# Connectors.net
KiCad netlist of a schematic drawn in Altium Designer
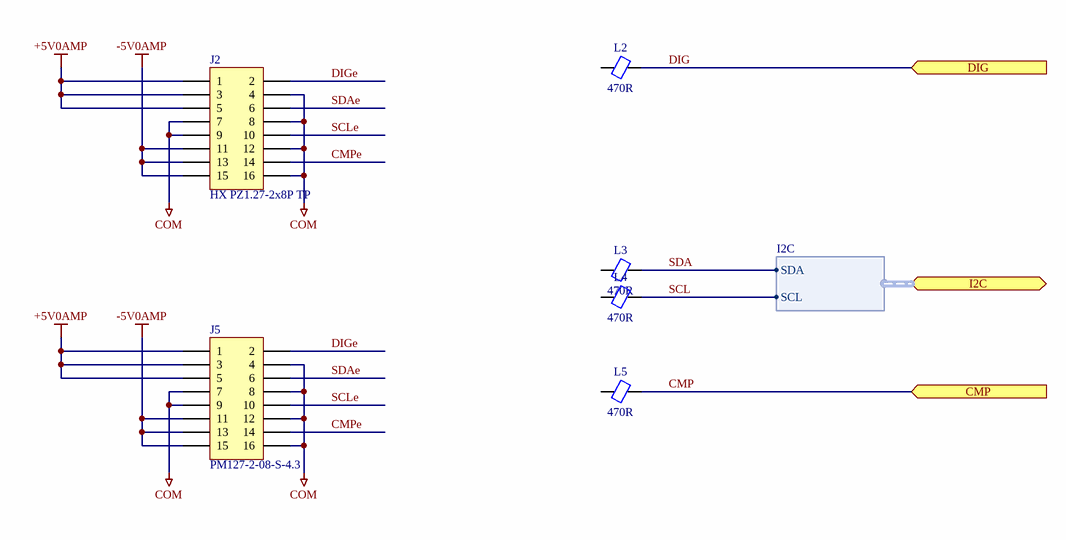
[diagram p0: Connectors.SchDoc]

(export (version "E")
  (design (tool "Eeschema 10.0.6"))
  (components
    (comp (ref "J2")
      (value "HX PZ1.27-2x8P TP")
      (footprint "HANXIA_HX PZ1.27-2x8P TP")
      (description "CONN HEADER 16POS 1.27mm DUAL ROW SMD")
      (fields (field (name "VENDOR 1 PART NUMBER") "C41376040") (field (name "CREATEDBY") "Judd Foster"))
      (libsource (lib "Component Library") (part "CONN,Hdr,2x8 Pin,1.27mm,SMD"))
    )
    (comp (ref "J5")
      (value "PM127-2-08-S-4.3")
      (footprint "HCTL_PM127-2-08-S-4.3")
      (description "CONN SOCKET 16POS 1.27mm DUAL ROW SMD")
      (fields (field (name "VENDOR 1 PART NUMBER") "C3975134") (field (name "CREATEDBY") "Judd Foster"))
      (libsource (lib "Component Library") (part "CONN,Rcpt,2x8 Pin,1.27mm,SMD"))
    )
    (comp (ref "L2")
      (value "470R")
      (footprint "INDC1005X05N")
      (description "470 Ohms @ 100 MHz 1 Power Line Ferrite Bead 0402 (1005 Metric) 1A 200mOhm")
      (fields
        (field (name "MANUFACTURER 1 PART NUMBER") "BLM15PX471SN1D")
        (field (name "VENDOR 1 PART NUMBER") "490-10662-1-ND")
        (field (name "CREATEDBY") "Judd Foster")
      )
      (libsource (lib "Component Library") (part "Ferrite,470R@100MHz,0402"))
    )
    (comp (ref "L3")
      (value "470R")
      (footprint "INDC1005X05N")
      (description "470 Ohms @ 100 MHz 1 Power Line Ferrite Bead 0402 (1005 Metric) 1A 200mOhm")
      (fields
        (field (name "MANUFACTURER 1 PART NUMBER") "BLM15PX471SN1D")
        (field (name "VENDOR 1 PART NUMBER") "490-10662-1-ND")
        (field (name "CREATEDBY") "Judd Foster")
      )
      (libsource (lib "Component Library") (part "Ferrite,470R@100MHz,0402"))
    )
    (comp (ref "L4")
      (value "470R")
      (footprint "INDC1005X05N")
      (description "470 Ohms @ 100 MHz 1 Power Line Ferrite Bead 0402 (1005 Metric) 1A 200mOhm")
      (fields
        (field (name "MANUFACTURER 1 PART NUMBER") "BLM15PX471SN1D")
        (field (name "VENDOR 1 PART NUMBER") "490-10662-1-ND")
        (field (name "CREATEDBY") "Judd Foster")
      )
      (libsource (lib "Component Library") (part "Ferrite,470R@100MHz,0402"))
    )
    (comp (ref "L5")
      (value "470R")
      (footprint "INDC1005X05N")
      (description "470 Ohms @ 100 MHz 1 Power Line Ferrite Bead 0402 (1005 Metric) 1A 200mOhm")
      (fields
        (field (name "MANUFACTURER 1 PART NUMBER") "BLM15PX471SN1D")
        (field (name "VENDOR 1 PART NUMBER") "490-10662-1-ND")
        (field (name "CREATEDBY") "Judd Foster")
      )
      (libsource (lib "Component Library") (part "Ferrite,470R@100MHz,0402"))
    )
  )
  (nets
    (net (code "2") (name "+5V0AMP") (class "Default")
      (node (ref "J2") (pin "1") (pinfunction "1_1") (pintype "passive"))
      (node (ref "J2") (pin "3") (pinfunction "3_3") (pintype "power_in"))
      (node (ref "J2") (pin "5") (pinfunction "5_5") (pintype "power_in"))
      (node (ref "J5") (pin "1") (pinfunction "1_1") (pintype "passive"))
      (node (ref "J5") (pin "3") (pinfunction "3_3") (pintype "power_in"))
      (node (ref "J5") (pin "5") (pinfunction "5_5") (pintype "power_in"))
    )
    (net (code "3") (name "-5V0AMP") (class "Default")
      (node (ref "J2") (pin "11") (pinfunction "11_11") (pintype "power_in"))
      (node (ref "J2") (pin "13") (pinfunction "13_13") (pintype "power_in"))
      (node (ref "J2") (pin "15") (pinfunction "15_15") (pintype "power_in"))
      (node (ref "J5") (pin "11") (pinfunction "11_11") (pintype "power_in"))
      (node (ref "J5") (pin "13") (pinfunction "13_13") (pintype "power_in"))
      (node (ref "J5") (pin "15") (pinfunction "15_15") (pintype "power_in"))
    )
    (net (code "4") (name "/CMP") (class "Default")
      (node (ref "L5") (pin "2") (pinfunction "2_2") (pintype "passive"))
    )
    (net (code "5") (name "/CMPe") (class "Default")
      (node (ref "J2") (pin "14") (pinfunction "14_14") (pintype "power_in"))
      (node (ref "J5") (pin "14") (pinfunction "14_14") (pintype "power_in"))
    )
    (net (code "6") (name "/DIG") (class "Default")
      (node (ref "L2") (pin "2") (pinfunction "2_2") (pintype "passive"))
    )
    (net (code "7") (name "/DIGe") (class "Default")
      (node (ref "J2") (pin "2") (pinfunction "2_2") (pintype "passive"))
      (node (ref "J5") (pin "2") (pinfunction "2_2") (pintype "passive"))
    )
    (net (code "8") (name "/SCL") (class "Default")
      (node (ref "L4") (pin "2") (pinfunction "2_2") (pintype "passive"))
    )
    (net (code "9") (name "/SCLe") (class "Default")
      (node (ref "J2") (pin "10") (pinfunction "10_10") (pintype "power_in"))
      (node (ref "J5") (pin "10") (pinfunction "10_10") (pintype "power_in"))
    )
    (net (code "10") (name "/SDA") (class "Default")
      (node (ref "L3") (pin "2") (pinfunction "2_2") (pintype "passive"))
    )
    (net (code "11") (name "/SDAe") (class "Default")
      (node (ref "J2") (pin "6") (pinfunction "6_6") (pintype "power_in"))
      (node (ref "J5") (pin "6") (pinfunction "6_6") (pintype "power_in"))
    )
    (net (code "13") (name "COM") (class "Default")
      (node (ref "J2") (pin "12") (pinfunction "12_12") (pintype "power_in"))
      (node (ref "J2") (pin "16") (pinfunction "16_16") (pintype "power_in"))
      (node (ref "J2") (pin "4") (pinfunction "4_4") (pintype "power_in"))
      (node (ref "J2") (pin "7") (pinfunction "7_7") (pintype "power_in"))
      (node (ref "J2") (pin "8") (pinfunction "8_8") (pintype "power_in"))
      (node (ref "J2") (pin "9") (pinfunction "9_9") (pintype "power_in"))
      (node (ref "J5") (pin "12") (pinfunction "12_12") (pintype "power_in"))
      (node (ref "J5") (pin "16") (pinfunction "16_16") (pintype "power_in"))
      (node (ref "J5") (pin "4") (pinfunction "4_4") (pintype "power_in"))
      (node (ref "J5") (pin "7") (pinfunction "7_7") (pintype "power_in"))
      (node (ref "J5") (pin "8") (pinfunction "8_8") (pintype "power_in"))
      (node (ref "J5") (pin "9") (pinfunction "9_9") (pintype "power_in"))
    )
    (net (code "14") (name "unconnected-(L2-Pad1)") (class "Default")
      (node (ref "L2") (pin "1") (pinfunction "1_1") (pintype "passive"))
    )
    (net (code "15") (name "unconnected-(L3-Pad1)") (class "Default")
      (node (ref "L3") (pin "1") (pinfunction "1_1") (pintype "passive"))
    )
    (net (code "16") (name "unconnected-(L4-Pad1)") (class "Default")
      (node (ref "L4") (pin "1") (pinfunction "1_1") (pintype "passive"))
    )
    (net (code "17") (name "unconnected-(L5-Pad1)") (class "Default")
      (node (ref "L5") (pin "1") (pinfunction "1_1") (pintype "passive"))
    )
  )
)
